# esp12extension.net
KiCad netlist of a schematic drawn in EAGLE
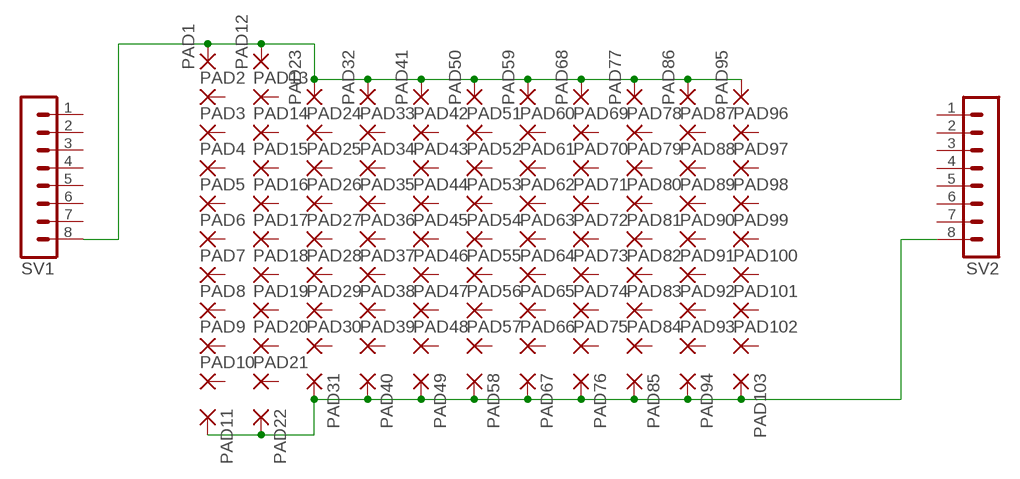
[diagram p0: schematic, sheet 1]

(export (version "E")
  (design (tool "Eeschema 10.0.6"))
  (components
    (comp (ref "PAD1")
      (value "1,6/0,8")
      (footprint "eagle-import:1,6_0,8")
      (libsource (lib "eagle-import") (part "1,6/0,8"))
    )
    (comp (ref "PAD2")
      (value "1,6/0,8")
      (footprint "eagle-import:1,6_0,8")
      (libsource (lib "eagle-import") (part "1,6/0,8"))
    )
    (comp (ref "PAD3")
      (value "1,6/0,8")
      (footprint "eagle-import:1,6_0,8")
      (libsource (lib "eagle-import") (part "1,6/0,8"))
    )
    (comp (ref "PAD4")
      (value "1,6/0,8")
      (footprint "eagle-import:1,6_0,8")
      (libsource (lib "eagle-import") (part "1,6/0,8"))
    )
    (comp (ref "PAD5")
      (value "1,6/0,8")
      (footprint "eagle-import:1,6_0,8")
      (libsource (lib "eagle-import") (part "1,6/0,8"))
    )
    (comp (ref "PAD6")
      (value "1,6/0,8")
      (footprint "eagle-import:1,6_0,8")
      (libsource (lib "eagle-import") (part "1,6/0,8"))
    )
    (comp (ref "PAD7")
      (value "1,6/0,8")
      (footprint "eagle-import:1,6_0,8")
      (libsource (lib "eagle-import") (part "1,6/0,8"))
    )
    (comp (ref "PAD8")
      (value "1,6/0,8")
      (footprint "eagle-import:1,6_0,8")
      (libsource (lib "eagle-import") (part "1,6/0,8"))
    )
    (comp (ref "PAD9")
      (value "1,6/0,8")
      (footprint "eagle-import:1,6_0,8")
      (libsource (lib "eagle-import") (part "1,6/0,8"))
    )
    (comp (ref "PAD10")
      (value "1,6/0,8")
      (footprint "eagle-import:1,6_0,8")
      (libsource (lib "eagle-import") (part "1,6/0,8"))
    )
    (comp (ref "PAD11")
      (value "1,6/0,8")
      (footprint "eagle-import:1,6_0,8")
      (libsource (lib "eagle-import") (part "1,6/0,8"))
    )
    (comp (ref "PAD12")
      (value "1,6/0,8")
      (footprint "eagle-import:1,6_0,8")
      (libsource (lib "eagle-import") (part "1,6/0,8"))
    )
    (comp (ref "PAD13")
      (value "1,6/0,8")
      (footprint "eagle-import:1,6_0,8")
      (libsource (lib "eagle-import") (part "1,6/0,8"))
    )
    (comp (ref "PAD14")
      (value "1,6/0,8")
      (footprint "eagle-import:1,6_0,8")
      (libsource (lib "eagle-import") (part "1,6/0,8"))
    )
    (comp (ref "PAD15")
      (value "1,6/0,8")
      (footprint "eagle-import:1,6_0,8")
      (libsource (lib "eagle-import") (part "1,6/0,8"))
    )
    (comp (ref "PAD16")
      (value "1,6/0,8")
      (footprint "eagle-import:1,6_0,8")
      (libsource (lib "eagle-import") (part "1,6/0,8"))
    )
    (comp (ref "PAD17")
      (value "1,6/0,8")
      (footprint "eagle-import:1,6_0,8")
      (libsource (lib "eagle-import") (part "1,6/0,8"))
    )
    (comp (ref "PAD18")
      (value "1,6/0,8")
      (footprint "eagle-import:1,6_0,8")
      (libsource (lib "eagle-import") (part "1,6/0,8"))
    )
    (comp (ref "PAD19")
      (value "1,6/0,8")
      (footprint "eagle-import:1,6_0,8")
      (libsource (lib "eagle-import") (part "1,6/0,8"))
    )
    (comp (ref "PAD20")
      (value "1,6/0,8")
      (footprint "eagle-import:1,6_0,8")
      (libsource (lib "eagle-import") (part "1,6/0,8"))
    )
    (comp (ref "PAD21")
      (value "1,6/0,8")
      (footprint "eagle-import:1,6_0,8")
      (libsource (lib "eagle-import") (part "1,6/0,8"))
    )
    (comp (ref "PAD22")
      (value "1,6/0,8")
      (footprint "eagle-import:1,6_0,8")
      (libsource (lib "eagle-import") (part "1,6/0,8"))
    )
    (comp (ref "PAD23")
      (value "1,6/0,8")
      (footprint "eagle-import:1,6_0,8")
      (libsource (lib "eagle-import") (part "1,6/0,8"))
    )
    (comp (ref "PAD24")
      (value "1,6/0,8")
      (footprint "eagle-import:1,6_0,8")
      (libsource (lib "eagle-import") (part "1,6/0,8"))
    )
    (comp (ref "PAD25")
      (value "1,6/0,8")
      (footprint "eagle-import:1,6_0,8")
      (libsource (lib "eagle-import") (part "1,6/0,8"))
    )
    (comp (ref "PAD26")
      (value "1,6/0,8")
      (footprint "eagle-import:1,6_0,8")
      (libsource (lib "eagle-import") (part "1,6/0,8"))
    )
    (comp (ref "PAD27")
      (value "1,6/0,8")
      (footprint "eagle-import:1,6_0,8")
      (libsource (lib "eagle-import") (part "1,6/0,8"))
    )
    (comp (ref "PAD28")
      (value "1,6/0,8")
      (footprint "eagle-import:1,6_0,8")
      (libsource (lib "eagle-import") (part "1,6/0,8"))
    )
    (comp (ref "PAD29")
      (value "1,6/0,8")
      (footprint "eagle-import:1,6_0,8")
      (libsource (lib "eagle-import") (part "1,6/0,8"))
    )
    (comp (ref "PAD30")
      (value "1,6/0,8")
      (footprint "eagle-import:1,6_0,8")
      (libsource (lib "eagle-import") (part "1,6/0,8"))
    )
    (comp (ref "PAD31")
      (value "1,6/0,8")
      (footprint "eagle-import:1,6_0,8")
      (libsource (lib "eagle-import") (part "1,6/0,8"))
    )
    (comp (ref "PAD32")
      (value "1,6/0,8")
      (footprint "eagle-import:1,6_0,8")
      (libsource (lib "eagle-import") (part "1,6/0,8"))
    )
    (comp (ref "PAD33")
      (value "1,6/0,8")
      (footprint "eagle-import:1,6_0,8")
      (libsource (lib "eagle-import") (part "1,6/0,8"))
    )
    (comp (ref "PAD34")
      (value "1,6/0,8")
      (footprint "eagle-import:1,6_0,8")
      (libsource (lib "eagle-import") (part "1,6/0,8"))
    )
    (comp (ref "PAD35")
      (value "1,6/0,8")
      (footprint "eagle-import:1,6_0,8")
      (libsource (lib "eagle-import") (part "1,6/0,8"))
    )
    (comp (ref "PAD36")
      (value "1,6/0,8")
      (footprint "eagle-import:1,6_0,8")
      (libsource (lib "eagle-import") (part "1,6/0,8"))
    )
    (comp (ref "PAD37")
      (value "1,6/0,8")
      (footprint "eagle-import:1,6_0,8")
      (libsource (lib "eagle-import") (part "1,6/0,8"))
    )
    (comp (ref "PAD38")
      (value "1,6/0,8")
      (footprint "eagle-import:1,6_0,8")
      (libsource (lib "eagle-import") (part "1,6/0,8"))
    )
    (comp (ref "PAD39")
      (value "1,6/0,8")
      (footprint "eagle-import:1,6_0,8")
      (libsource (lib "eagle-import") (part "1,6/0,8"))
    )
    (comp (ref "PAD40")
      (value "1,6/0,8")
      (footprint "eagle-import:1,6_0,8")
      (libsource (lib "eagle-import") (part "1,6/0,8"))
    )
    (comp (ref "PAD41")
      (value "1,6/0,8")
      (footprint "eagle-import:1,6_0,8")
      (libsource (lib "eagle-import") (part "1,6/0,8"))
    )
    (comp (ref "PAD42")
      (value "1,6/0,8")
      (footprint "eagle-import:1,6_0,8")
      (libsource (lib "eagle-import") (part "1,6/0,8"))
    )
    (comp (ref "PAD43")
      (value "1,6/0,8")
      (footprint "eagle-import:1,6_0,8")
      (libsource (lib "eagle-import") (part "1,6/0,8"))
    )
    (comp (ref "PAD44")
      (value "1,6/0,8")
      (footprint "eagle-import:1,6_0,8")
      (libsource (lib "eagle-import") (part "1,6/0,8"))
    )
    (comp (ref "PAD45")
      (value "1,6/0,8")
      (footprint "eagle-import:1,6_0,8")
      (libsource (lib "eagle-import") (part "1,6/0,8"))
    )
    (comp (ref "PAD46")
      (value "1,6/0,8")
      (footprint "eagle-import:1,6_0,8")
      (libsource (lib "eagle-import") (part "1,6/0,8"))
    )
    (comp (ref "PAD47")
      (value "1,6/0,8")
      (footprint "eagle-import:1,6_0,8")
      (libsource (lib "eagle-import") (part "1,6/0,8"))
    )
    (comp (ref "PAD48")
      (value "1,6/0,8")
      (footprint "eagle-import:1,6_0,8")
      (libsource (lib "eagle-import") (part "1,6/0,8"))
    )
    (comp (ref "PAD49")
      (value "1,6/0,8")
      (footprint "eagle-import:1,6_0,8")
      (libsource (lib "eagle-import") (part "1,6/0,8"))
    )
    (comp (ref "PAD50")
      (value "1,6/0,8")
      (footprint "eagle-import:1,6_0,8")
      (libsource (lib "eagle-import") (part "1,6/0,8"))
    )
    (comp (ref "PAD51")
      (value "1,6/0,8")
      (footprint "eagle-import:1,6_0,8")
      (libsource (lib "eagle-import") (part "1,6/0,8"))
    )
    (comp (ref "PAD52")
      (value "1,6/0,8")
      (footprint "eagle-import:1,6_0,8")
      (libsource (lib "eagle-import") (part "1,6/0,8"))
    )
    (comp (ref "PAD53")
      (value "1,6/0,8")
      (footprint "eagle-import:1,6_0,8")
      (libsource (lib "eagle-import") (part "1,6/0,8"))
    )
    (comp (ref "PAD54")
      (value "1,6/0,8")
      (footprint "eagle-import:1,6_0,8")
      (libsource (lib "eagle-import") (part "1,6/0,8"))
    )
    (comp (ref "PAD55")
      (value "1,6/0,8")
      (footprint "eagle-import:1,6_0,8")
      (libsource (lib "eagle-import") (part "1,6/0,8"))
    )
    (comp (ref "PAD56")
      (value "1,6/0,8")
      (footprint "eagle-import:1,6_0,8")
      (libsource (lib "eagle-import") (part "1,6/0,8"))
    )
    (comp (ref "PAD57")
      (value "1,6/0,8")
      (footprint "eagle-import:1,6_0,8")
      (libsource (lib "eagle-import") (part "1,6/0,8"))
    )
    (comp (ref "PAD58")
      (value "1,6/0,8")
      (footprint "eagle-import:1,6_0,8")
      (libsource (lib "eagle-import") (part "1,6/0,8"))
    )
    (comp (ref "PAD59")
      (value "1,6/0,8")
      (footprint "eagle-import:1,6_0,8")
      (libsource (lib "eagle-import") (part "1,6/0,8"))
    )
    (comp (ref "PAD60")
      (value "1,6/0,8")
      (footprint "eagle-import:1,6_0,8")
      (libsource (lib "eagle-import") (part "1,6/0,8"))
    )
    (comp (ref "PAD61")
      (value "1,6/0,8")
      (footprint "eagle-import:1,6_0,8")
      (libsource (lib "eagle-import") (part "1,6/0,8"))
    )
    (comp (ref "PAD62")
      (value "1,6/0,8")
      (footprint "eagle-import:1,6_0,8")
      (libsource (lib "eagle-import") (part "1,6/0,8"))
    )
    (comp (ref "PAD63")
      (value "1,6/0,8")
      (footprint "eagle-import:1,6_0,8")
      (libsource (lib "eagle-import") (part "1,6/0,8"))
    )
    (comp (ref "PAD64")
      (value "1,6/0,8")
      (footprint "eagle-import:1,6_0,8")
      (libsource (lib "eagle-import") (part "1,6/0,8"))
    )
    (comp (ref "PAD65")
      (value "1,6/0,8")
      (footprint "eagle-import:1,6_0,8")
      (libsource (lib "eagle-import") (part "1,6/0,8"))
    )
    (comp (ref "PAD66")
      (value "1,6/0,8")
      (footprint "eagle-import:1,6_0,8")
      (libsource (lib "eagle-import") (part "1,6/0,8"))
    )
    (comp (ref "PAD67")
      (value "1,6/0,8")
      (footprint "eagle-import:1,6_0,8")
      (libsource (lib "eagle-import") (part "1,6/0,8"))
    )
    (comp (ref "PAD68")
      (value "1,6/0,8")
      (footprint "eagle-import:1,6_0,8")
      (libsource (lib "eagle-import") (part "1,6/0,8"))
    )
    (comp (ref "PAD69")
      (value "1,6/0,8")
      (footprint "eagle-import:1,6_0,8")
      (libsource (lib "eagle-import") (part "1,6/0,8"))
    )
    (comp (ref "PAD70")
      (value "1,6/0,8")
      (footprint "eagle-import:1,6_0,8")
      (libsource (lib "eagle-import") (part "1,6/0,8"))
    )
    (comp (ref "PAD71")
      (value "1,6/0,8")
      (footprint "eagle-import:1,6_0,8")
      (libsource (lib "eagle-import") (part "1,6/0,8"))
    )
    (comp (ref "PAD72")
      (value "1,6/0,8")
      (footprint "eagle-import:1,6_0,8")
      (libsource (lib "eagle-import") (part "1,6/0,8"))
    )
    (comp (ref "PAD73")
      (value "1,6/0,8")
      (footprint "eagle-import:1,6_0,8")
      (libsource (lib "eagle-import") (part "1,6/0,8"))
    )
    (comp (ref "PAD74")
      (value "1,6/0,8")
      (footprint "eagle-import:1,6_0,8")
      (libsource (lib "eagle-import") (part "1,6/0,8"))
    )
    (comp (ref "PAD75")
      (value "1,6/0,8")
      (footprint "eagle-import:1,6_0,8")
      (libsource (lib "eagle-import") (part "1,6/0,8"))
    )
    (comp (ref "PAD76")
      (value "1,6/0,8")
      (footprint "eagle-import:1,6_0,8")
      (libsource (lib "eagle-import") (part "1,6/0,8"))
    )
    (comp (ref "PAD77")
      (value "1,6/0,8")
      (footprint "eagle-import:1,6_0,8")
      (libsource (lib "eagle-import") (part "1,6/0,8"))
    )
    (comp (ref "PAD78")
      (value "1,6/0,8")
      (footprint "eagle-import:1,6_0,8")
      (libsource (lib "eagle-import") (part "1,6/0,8"))
    )
    (comp (ref "PAD79")
      (value "1,6/0,8")
      (footprint "eagle-import:1,6_0,8")
      (libsource (lib "eagle-import") (part "1,6/0,8"))
    )
    (comp (ref "PAD80")
      (value "1,6/0,8")
      (footprint "eagle-import:1,6_0,8")
      (libsource (lib "eagle-import") (part "1,6/0,8"))
    )
    (comp (ref "PAD81")
      (value "1,6/0,8")
      (footprint "eagle-import:1,6_0,8")
      (libsource (lib "eagle-import") (part "1,6/0,8"))
    )
    (comp (ref "PAD82")
      (value "1,6/0,8")
      (footprint "eagle-import:1,6_0,8")
      (libsource (lib "eagle-import") (part "1,6/0,8"))
    )
    (comp (ref "PAD83")
      (value "1,6/0,8")
      (footprint "eagle-import:1,6_0,8")
      (libsource (lib "eagle-import") (part "1,6/0,8"))
    )
    (comp (ref "PAD84")
      (value "1,6/0,8")
      (footprint "eagle-import:1,6_0,8")
      (libsource (lib "eagle-import") (part "1,6/0,8"))
    )
    (comp (ref "PAD85")
      (value "1,6/0,8")
      (footprint "eagle-import:1,6_0,8")
      (libsource (lib "eagle-import") (part "1,6/0,8"))
    )
    (comp (ref "PAD86")
      (value "1,6/0,8")
      (footprint "eagle-import:1,6_0,8")
      (libsource (lib "eagle-import") (part "1,6/0,8"))
    )
    (comp (ref "PAD87")
      (value "1,6/0,8")
      (footprint "eagle-import:1,6_0,8")
      (libsource (lib "eagle-import") (part "1,6/0,8"))
    )
    (comp (ref "PAD88")
      (value "1,6/0,8")
      (footprint "eagle-import:1,6_0,8")
      (libsource (lib "eagle-import") (part "1,6/0,8"))
    )
    (comp (ref "PAD89")
      (value "1,6/0,8")
      (footprint "eagle-import:1,6_0,8")
      (libsource (lib "eagle-import") (part "1,6/0,8"))
    )
    (comp (ref "PAD90")
      (value "1,6/0,8")
      (footprint "eagle-import:1,6_0,8")
      (libsource (lib "eagle-import") (part "1,6/0,8"))
    )
    (comp (ref "PAD91")
      (value "1,6/0,8")
      (footprint "eagle-import:1,6_0,8")
      (libsource (lib "eagle-import") (part "1,6/0,8"))
    )
    (comp (ref "PAD92")
      (value "1,6/0,8")
      (footprint "eagle-import:1,6_0,8")
      (libsource (lib "eagle-import") (part "1,6/0,8"))
    )
    (comp (ref "PAD93")
      (value "1,6/0,8")
      (footprint "eagle-import:1,6_0,8")
      (libsource (lib "eagle-import") (part "1,6/0,8"))
    )
    (comp (ref "PAD94")
      (value "1,6/0,8")
      (footprint "eagle-import:1,6_0,8")
      (libsource (lib "eagle-import") (part "1,6/0,8"))
    )
    (comp (ref "PAD95")
      (value "1,6/0,8")
      (footprint "eagle-import:1,6_0,8")
      (libsource (lib "eagle-import") (part "1,6/0,8"))
    )
    (comp (ref "PAD96")
      (value "1,6/0,8")
      (footprint "eagle-import:1,6_0,8")
      (libsource (lib "eagle-import") (part "1,6/0,8"))
    )
    (comp (ref "PAD97")
      (value "1,6/0,8")
      (footprint "eagle-import:1,6_0,8")
      (libsource (lib "eagle-import") (part "1,6/0,8"))
    )
    (comp (ref "PAD98")
      (value "1,6/0,8")
      (footprint "eagle-import:1,6_0,8")
      (libsource (lib "eagle-import") (part "1,6/0,8"))
    )
    (comp (ref "PAD99")
      (value "1,6/0,8")
      (footprint "eagle-import:1,6_0,8")
      (libsource (lib "eagle-import") (part "1,6/0,8"))
    )
    (comp (ref "PAD100")
      (value "1,6/0,8")
      (footprint "eagle-import:1,6_0,8")
      (libsource (lib "eagle-import") (part "1,6/0,8"))
    )
    (comp (ref "PAD101")
      (value "1,6/0,8")
      (footprint "eagle-import:1,6_0,8")
      (libsource (lib "eagle-import") (part "1,6/0,8"))
    )
    (comp (ref "PAD102")
      (value "1,6/0,8")
      (footprint "eagle-import:1,6_0,8")
      (libsource (lib "eagle-import") (part "1,6/0,8"))
    )
    (comp (ref "PAD103")
      (value "1,6/0,8")
      (footprint "eagle-import:1,6_0,8")
      (libsource (lib "eagle-import") (part "1,6/0,8"))
    )
    (comp (ref "SV1")
      (value "MA08-1")
      (footprint "eagle-import:MA08-1")
      (libsource (lib "eagle-import") (part "MA08-1"))
    )
    (comp (ref "SV2")
      (value "MA08-1")
      (footprint "eagle-import:MA08-1")
      (libsource (lib "eagle-import") (part "MA08-1"))
    )
  )
  (nets
    (net (code "1") (name "Net-(PAD1-P)") (class "Default")
      (node (ref "PAD1") (pin "1") (pinfunction "P_1") (pintype "passive"))
      (node (ref "PAD12") (pin "1") (pinfunction "P_1") (pintype "passive"))
      (node (ref "PAD23") (pin "1") (pinfunction "P_1") (pintype "passive"))
      (node (ref "PAD32") (pin "1") (pinfunction "P_1") (pintype "passive"))
      (node (ref "PAD41") (pin "1") (pinfunction "P_1") (pintype "passive"))
      (node (ref "PAD50") (pin "1") (pinfunction "P_1") (pintype "passive"))
      (node (ref "PAD59") (pin "1") (pinfunction "P_1") (pintype "passive"))
      (node (ref "PAD68") (pin "1") (pinfunction "P_1") (pintype "passive"))
      (node (ref "PAD77") (pin "1") (pinfunction "P_1") (pintype "passive"))
      (node (ref "PAD86") (pin "1") (pinfunction "P_1") (pintype "passive"))
      (node (ref "PAD95") (pin "1") (pinfunction "P_1") (pintype "passive"))
      (node (ref "SV1") (pin "8") (pinfunction "8_8") (pintype "passive"))
    )
    (net (code "2") (name "Net-(PAD103-P)") (class "Default")
      (node (ref "PAD103") (pin "1") (pinfunction "P_1") (pintype "passive"))
      (node (ref "PAD11") (pin "1") (pinfunction "P_1") (pintype "passive"))
      (node (ref "PAD22") (pin "1") (pinfunction "P_1") (pintype "passive"))
      (node (ref "PAD31") (pin "1") (pinfunction "P_1") (pintype "passive"))
      (node (ref "PAD40") (pin "1") (pinfunction "P_1") (pintype "passive"))
      (node (ref "PAD49") (pin "1") (pinfunction "P_1") (pintype "passive"))
      (node (ref "PAD58") (pin "1") (pinfunction "P_1") (pintype "passive"))
      (node (ref "PAD67") (pin "1") (pinfunction "P_1") (pintype "passive"))
      (node (ref "PAD76") (pin "1") (pinfunction "P_1") (pintype "passive"))
      (node (ref "PAD85") (pin "1") (pinfunction "P_1") (pintype "passive"))
      (node (ref "PAD94") (pin "1") (pinfunction "P_1") (pintype "passive"))
      (node (ref "SV2") (pin "8") (pinfunction "8_8") (pintype "passive"))
    )
    (net (code "3") (name "unconnected-(PAD2-P-Pad1)") (class "Default")
      (node (ref "PAD2") (pin "1") (pinfunction "P_1") (pintype "passive"))
    )
    (net (code "4") (name "unconnected-(PAD3-P-Pad1)") (class "Default")
      (node (ref "PAD3") (pin "1") (pinfunction "P_1") (pintype "passive"))
    )
    (net (code "5") (name "unconnected-(PAD4-P-Pad1)") (class "Default")
      (node (ref "PAD4") (pin "1") (pinfunction "P_1") (pintype "passive"))
    )
    (net (code "6") (name "unconnected-(PAD5-P-Pad1)") (class "Default")
      (node (ref "PAD5") (pin "1") (pinfunction "P_1") (pintype "passive"))
    )
    (net (code "7") (name "unconnected-(PAD6-P-Pad1)") (class "Default")
      (node (ref "PAD6") (pin "1") (pinfunction "P_1") (pintype "passive"))
    )
    (net (code "8") (name "unconnected-(PAD7-P-Pad1)") (class "Default")
      (node (ref "PAD7") (pin "1") (pinfunction "P_1") (pintype "passive"))
    )
    (net (code "9") (name "unconnected-(PAD8-P-Pad1)") (class "Default")
      (node (ref "PAD8") (pin "1") (pinfunction "P_1") (pintype "passive"))
    )
    (net (code "10") (name "unconnected-(PAD9-P-Pad1)") (class "Default")
      (node (ref "PAD9") (pin "1") (pinfunction "P_1") (pintype "passive"))
    )
    (net (code "11") (name "unconnected-(PAD10-P-Pad1)") (class "Default")
      (node (ref "PAD10") (pin "1") (pinfunction "P_1") (pintype "passive"))
    )
    (net (code "12") (name "unconnected-(PAD13-P-Pad1)") (class "Default")
      (node (ref "PAD13") (pin "1") (pinfunction "P_1") (pintype "passive"))
    )
    (net (code "13") (name "unconnected-(PAD14-P-Pad1)") (class "Default")
      (node (ref "PAD14") (pin "1") (pinfunction "P_1") (pintype "passive"))
    )
    (net (code "14") (name "unconnected-(PAD15-P-Pad1)") (class "Default")
      (node (ref "PAD15") (pin "1") (pinfunction "P_1") (pintype "passive"))
    )
    (net (code "15") (name "unconnected-(PAD16-P-Pad1)") (class "Default")
      (node (ref "PAD16") (pin "1") (pinfunction "P_1") (pintype "passive"))
    )
    (net (code "16") (name "unconnected-(PAD17-P-Pad1)") (class "Default")
      (node (ref "PAD17") (pin "1") (pinfunction "P_1") (pintype "passive"))
    )
    (net (code "17") (name "unconnected-(PAD18-P-Pad1)") (class "Default")
      (node (ref "PAD18") (pin "1") (pinfunction "P_1") (pintype "passive"))
    )
    (net (code "18") (name "unconnected-(PAD19-P-Pad1)") (class "Default")
      (node (ref "PAD19") (pin "1") (pinfunction "P_1") (pintype "passive"))
    )
    (net (code "19") (name "unconnected-(PAD20-P-Pad1)") (class "Default")
      (node (ref "PAD20") (pin "1") (pinfunction "P_1") (pintype "passive"))
    )
    (net (code "20") (name "unconnected-(PAD21-P-Pad1)") (class "Default")
      (node (ref "PAD21") (pin "1") (pinfunction "P_1") (pintype "passive"))
    )
    (net (code "21") (name "unconnected-(PAD24-P-Pad1)") (class "Default")
      (node (ref "PAD24") (pin "1") (pinfunction "P_1") (pintype "passive"))
    )
    (net (code "22") (name "unconnected-(PAD25-P-Pad1)") (class "Default")
      (node (ref "PAD25") (pin "1") (pinfunction "P_1") (pintype "passive"))
    )
    (net (code "23") (name "unconnected-(PAD26-P-Pad1)") (class "Default")
      (node (ref "PAD26") (pin "1") (pinfunction "P_1") (pintype "passive"))
    )
    (net (code "24") (name "unconnected-(PAD27-P-Pad1)") (class "Default")
      (node (ref "PAD27") (pin "1") (pinfunction "P_1") (pintype "passive"))
    )
    (net (code "25") (name "unconnected-(PAD28-P-Pad1)") (class "Default")
      (node (ref "PAD28") (pin "1") (pinfunction "P_1") (pintype "passive"))
    )
    (net (code "26") (name "unconnected-(PAD29-P-Pad1)") (class "Default")
      (node (ref "PAD29") (pin "1") (pinfunction "P_1") (pintype "passive"))
    )
    (net (code "27") (name "unconnected-(PAD30-P-Pad1)") (class "Default")
      (node (ref "PAD30") (pin "1") (pinfunction "P_1") (pintype "passive"))
    )
    (net (code "28") (name "unconnected-(PAD33-P-Pad1)") (class "Default")
      (node (ref "PAD33") (pin "1") (pinfunction "P_1") (pintype "passive"))
    )
    (net (code "29") (name "unconnected-(PAD34-P-Pad1)") (class "Default")
      (node (ref "PAD34") (pin "1") (pinfunction "P_1") (pintype "passive"))
    )
    (net (code "30") (name "unconnected-(PAD35-P-Pad1)") (class "Default")
      (node (ref "PAD35") (pin "1") (pinfunction "P_1") (pintype "passive"))
    )
    (net (code "31") (name "unconnected-(PAD36-P-Pad1)") (class "Default")
      (node (ref "PAD36") (pin "1") (pinfunction "P_1") (pintype "passive"))
    )
    (net (code "32") (name "unconnected-(PAD37-P-Pad1)") (class "Default")
      (node (ref "PAD37") (pin "1") (pinfunction "P_1") (pintype "passive"))
    )
    (net (code "33") (name "unconnected-(PAD38-P-Pad1)") (class "Default")
      (node (ref "PAD38") (pin "1") (pinfunction "P_1") (pintype "passive"))
    )
    (net (code "34") (name "unconnected-(PAD39-P-Pad1)") (class "Default")
      (node (ref "PAD39") (pin "1") (pinfunction "P_1") (pintype "passive"))
    )
    (net (code "35") (name "unconnected-(PAD42-P-Pad1)") (class "Default")
      (node (ref "PAD42") (pin "1") (pinfunction "P_1") (pintype "passive"))
    )
    (net (code "36") (name "unconnected-(PAD43-P-Pad1)") (class "Default")
      (node (ref "PAD43") (pin "1") (pinfunction "P_1") (pintype "passive"))
    )
    (net (code "37") (name "unconnected-(PAD44-P-Pad1)") (class "Default")
      (node (ref "PAD44") (pin "1") (pinfunction "P_1") (pintype "passive"))
    )
    (net (code "38") (name "unconnected-(PAD45-P-Pad1)") (class "Default")
      (node (ref "PAD45") (pin "1") (pinfunction "P_1") (pintype "passive"))
    )
    (net (code "39") (name "unconnected-(PAD46-P-Pad1)") (class "Default")
      (node (ref "PAD46") (pin "1") (pinfunction "P_1") (pintype "passive"))
    )
    (net (code "40") (name "unconnected-(PAD47-P-Pad1)") (class "Default")
      (node (ref "PAD47") (pin "1") (pinfunction "P_1") (pintype "passive"))
    )
    (net (code "41") (name "unconnected-(PAD48-P-Pad1)") (class "Default")
      (node (ref "PAD48") (pin "1") (pinfunction "P_1") (pintype "passive"))
    )
    (net (code "42") (name "unconnected-(PAD51-P-Pad1)") (class "Default")
      (node (ref "PAD51") (pin "1") (pinfunction "P_1") (pintype "passive"))
    )
    (net (code "43") (name "unconnected-(PAD52-P-Pad1)") (class "Default")
      (node (ref "PAD52") (pin "1") (pinfunction "P_1") (pintype "passive"))
    )
    (net (code "44") (name "unconnected-(PAD53-P-Pad1)") (class "Default")
      (node (ref "PAD53") (pin "1") (pinfunction "P_1") (pintype "passive"))
    )
    (net (code "45") (name "unconnected-(PAD54-P-Pad1)") (class "Default")
      (node (ref "PAD54") (pin "1") (pinfunction "P_1") (pintype "passive"))
    )
    (net (code "46") (name "unconnected-(PAD55-P-Pad1)") (class "Default")
      (node (ref "PAD55") (pin "1") (pinfunction "P_1") (pintype "passive"))
    )
    (net (code "47") (name "unconnected-(PAD56-P-Pad1)") (class "Default")
      (node (ref "PAD56") (pin "1") (pinfunction "P_1") (pintype "passive"))
    )
    (net (code "48") (name "unconnected-(PAD57-P-Pad1)") (class "Default")
      (node (ref "PAD57") (pin "1") (pinfunction "P_1") (pintype "passive"))
    )
    (net (code "49") (name "unconnected-(PAD60-P-Pad1)") (class "Default")
      (node (ref "PAD60") (pin "1") (pinfunction "P_1") (pintype "passive"))
    )
    (net (code "50") (name "unconnected-(PAD61-P-Pad1)") (class "Default")
      (node (ref "PAD61") (pin "1") (pinfunction "P_1") (pintype "passive"))
    )
    (net (code "51") (name "unconnected-(PAD62-P-Pad1)") (class "Default")
      (node (ref "PAD62") (pin "1") (pinfunction "P_1") (pintype "passive"))
    )
    (net (code "52") (name "unconnected-(PAD63-P-Pad1)") (class "Default")
      (node (ref "PAD63") (pin "1") (pinfunction "P_1") (pintype "passive"))
    )
    (net (code "53") (name "unconnected-(PAD64-P-Pad1)") (class "Default")
      (node (ref "PAD64") (pin "1") (pinfunction "P_1") (pintype "passive"))
    )
    (net (code "54") (name "unconnected-(PAD65-P-Pad1)") (class "Default")
      (node (ref "PAD65") (pin "1") (pinfunction "P_1") (pintype "passive"))
    )
    (net (code "55") (name "unconnected-(PAD66-P-Pad1)") (class "Default")
      (node (ref "PAD66") (pin "1") (pinfunction "P_1") (pintype "passive"))
    )
    (net (code "56") (name "unconnected-(PAD69-P-Pad1)") (class "Default")
      (node (ref "PAD69") (pin "1") (pinfunction "P_1") (pintype "passive"))
    )
    (net (code "57") (name "unconnected-(PAD70-P-Pad1)") (class "Default")
      (node (ref "PAD70") (pin "1") (pinfunction "P_1") (pintype "passive"))
    )
    (net (code "58") (name "unconnected-(PAD71-P-Pad1)") (class "Default")
      (node (ref "PAD71") (pin "1") (pinfunction "P_1") (pintype "passive"))
    )
    (net (code "59") (name "unconnected-(PAD72-P-Pad1)") (class "Default")
      (node (ref "PAD72") (pin "1") (pinfunction "P_1") (pintype "passive"))
    )
    (net (code "60") (name "unconnected-(PAD73-P-Pad1)") (class "Default")
      (node (ref "PAD73") (pin "1") (pinfunction "P_1") (pintype "passive"))
    )
    (net (code "61") (name "unconnected-(PAD74-P-Pad1)") (class "Default")
      (node (ref "PAD74") (pin "1") (pinfunction "P_1") (pintype "passive"))
    )
    (net (code "62") (name "unconnected-(PAD75-P-Pad1)") (class "Default")
      (node (ref "PAD75") (pin "1") (pinfunction "P_1") (pintype "passive"))
    )
    (net (code "63") (name "unconnected-(PAD78-P-Pad1)") (class "Default")
      (node (ref "PAD78") (pin "1") (pinfunction "P_1") (pintype "passive"))
    )
    (net (code "64") (name "unconnected-(PAD79-P-Pad1)") (class "Default")
      (node (ref "PAD79") (pin "1") (pinfunction "P_1") (pintype "passive"))
    )
    (net (code "65") (name "unconnected-(PAD80-P-Pad1)") (class "Default")
      (node (ref "PAD80") (pin "1") (pinfunction "P_1") (pintype "passive"))
    )
    (net (code "66") (name "unconnected-(PAD81-P-Pad1)") (class "Default")
      (node (ref "PAD81") (pin "1") (pinfunction "P_1") (pintype "passive"))
    )
    (net (code "67") (name "unconnected-(PAD82-P-Pad1)") (class "Default")
      (node (ref "PAD82") (pin "1") (pinfunction "P_1") (pintype "passive"))
    )
    (net (code "68") (name "unconnected-(PAD83-P-Pad1)") (class "Default")
      (node (ref "PAD83") (pin "1") (pinfunction "P_1") (pintype "passive"))
    )
    (net (code "69") (name "unconnected-(PAD84-P-Pad1)") (class "Default")
      (node (ref "PAD84") (pin "1") (pinfunction "P_1") (pintype "passive"))
    )
    (net (code "70") (name "unconnected-(PAD87-P-Pad1)") (class "Default")
      (node (ref "PAD87") (pin "1") (pinfunction "P_1") (pintype "passive"))
    )
    (net (code "71") (name "unconnected-(PAD88-P-Pad1)") (class "Default")
      (node (ref "PAD88") (pin "1") (pinfunction "P_1") (pintype "passive"))
    )
    (net (code "72") (name "unconnected-(PAD89-P-Pad1)") (class "Default")
      (node (ref "PAD89") (pin "1") (pinfunction "P_1") (pintype "passive"))
    )
    (net (code "73") (name "unconnected-(PAD90-P-Pad1)") (class "Default")
      (node (ref "PAD90") (pin "1") (pinfunction "P_1") (pintype "passive"))
    )
    (net (code "74") (name "unconnected-(PAD91-P-Pad1)") (class "Default")
      (node (ref "PAD91") (pin "1") (pinfunction "P_1") (pintype "passive"))
    )
    (net (code "75") (name "unconnected-(PAD92-P-Pad1)") (class "Default")
      (node (ref "PAD92") (pin "1") (pinfunction "P_1") (pintype "passive"))
    )
    (net (code "76") (name "unconnected-(PAD93-P-Pad1)") (class "Default")
      (node (ref "PAD93") (pin "1") (pinfunction "P_1") (pintype "passive"))
    )
    (net (code "77") (name "unconnected-(PAD96-P-Pad1)") (class "Default")
      (node (ref "PAD96") (pin "1") (pinfunction "P_1") (pintype "passive"))
    )
    (net (code "78") (name "unconnected-(PAD97-P-Pad1)") (class "Default")
      (node (ref "PAD97") (pin "1") (pinfunction "P_1") (pintype "passive"))
    )
    (net (code "79") (name "unconnected-(PAD98-P-Pad1)") (class "Default")
      (node (ref "PAD98") (pin "1") (pinfunction "P_1") (pintype "passive"))
    )
    (net (code "80") (name "unconnected-(PAD99-P-Pad1)") (class "Default")
      (node (ref "PAD99") (pin "1") (pinfunction "P_1") (pintype "passive"))
    )
    (net (code "81") (name "unconnected-(PAD100-P-Pad1)") (class "Default")
      (node (ref "PAD100") (pin "1") (pinfunction "P_1") (pintype "passive"))
    )
    (net (code "82") (name "unconnected-(PAD101-P-Pad1)") (class "Default")
      (node (ref "PAD101") (pin "1") (pinfunction "P_1") (pintype "passive"))
    )
    (net (code "83") (name "unconnected-(PAD102-P-Pad1)") (class "Default")
      (node (ref "PAD102") (pin "1") (pinfunction "P_1") (pintype "passive"))
    )
    (net (code "84") (name "unconnected-(SV1-Pad1)") (class "Default")
      (node (ref "SV1") (pin "1") (pinfunction "1_1") (pintype "passive"))
    )
    (net (code "85") (name "unconnected-(SV1-Pad2)") (class "Default")
      (node (ref "SV1") (pin "2") (pinfunction "2_2") (pintype "passive"))
    )
    (net (code "86") (name "unconnected-(SV1-Pad3)") (class "Default")
      (node (ref "SV1") (pin "3") (pinfunction "3_3") (pintype "passive"))
    )
    (net (code "87") (name "unconnected-(SV1-Pad4)") (class "Default")
      (node (ref "SV1") (pin "4") (pinfunction "4_4") (pintype "passive"))
    )
    (net (code "88") (name "unconnected-(SV1-Pad5)") (class "Default")
      (node (ref "SV1") (pin "5") (pinfunction "5_5") (pintype "passive"))
    )
    (net (code "89") (name "unconnected-(SV1-Pad6)") (class "Default")
      (node (ref "SV1") (pin "6") (pinfunction "6_6") (pintype "passive"))
    )
    (net (code "90") (name "unconnected-(SV1-Pad7)") (class "Default")
      (node (ref "SV1") (pin "7") (pinfunction "7_7") (pintype "passive"))
    )
    (net (code "91") (name "unconnected-(SV2-Pad1)") (class "Default")
      (node (ref "SV2") (pin "1") (pinfunction "1_1") (pintype "passive"))
    )
    (net (code "92") (name "unconnected-(SV2-Pad2)") (class "Default")
      (node (ref "SV2") (pin "2") (pinfunction "2_2") (pintype "passive"))
    )
    (net (code "93") (name "unconnected-(SV2-Pad3)") (class "Default")
      (node (ref "SV2") (pin "3") (pinfunction "3_3") (pintype "passive"))
    )
    (net (code "94") (name "unconnected-(SV2-Pad4)") (class "Default")
      (node (ref "SV2") (pin "4") (pinfunction "4_4") (pintype "passive"))
    )
    (net (code "95") (name "unconnected-(SV2-Pad5)") (class "Default")
      (node (ref "SV2") (pin "5") (pinfunction "5_5") (pintype "passive"))
    )
    (net (code "96") (name "unconnected-(SV2-Pad6)") (class "Default")
      (node (ref "SV2") (pin "6") (pinfunction "6_6") (pintype "passive"))
    )
    (net (code "97") (name "unconnected-(SV2-Pad7)") (class "Default")
      (node (ref "SV2") (pin "7") (pinfunction "7_7") (pintype "passive"))
    )
  )
)
